# Left_Glove.net
KiCad netlist of a schematic drawn in EAGLE
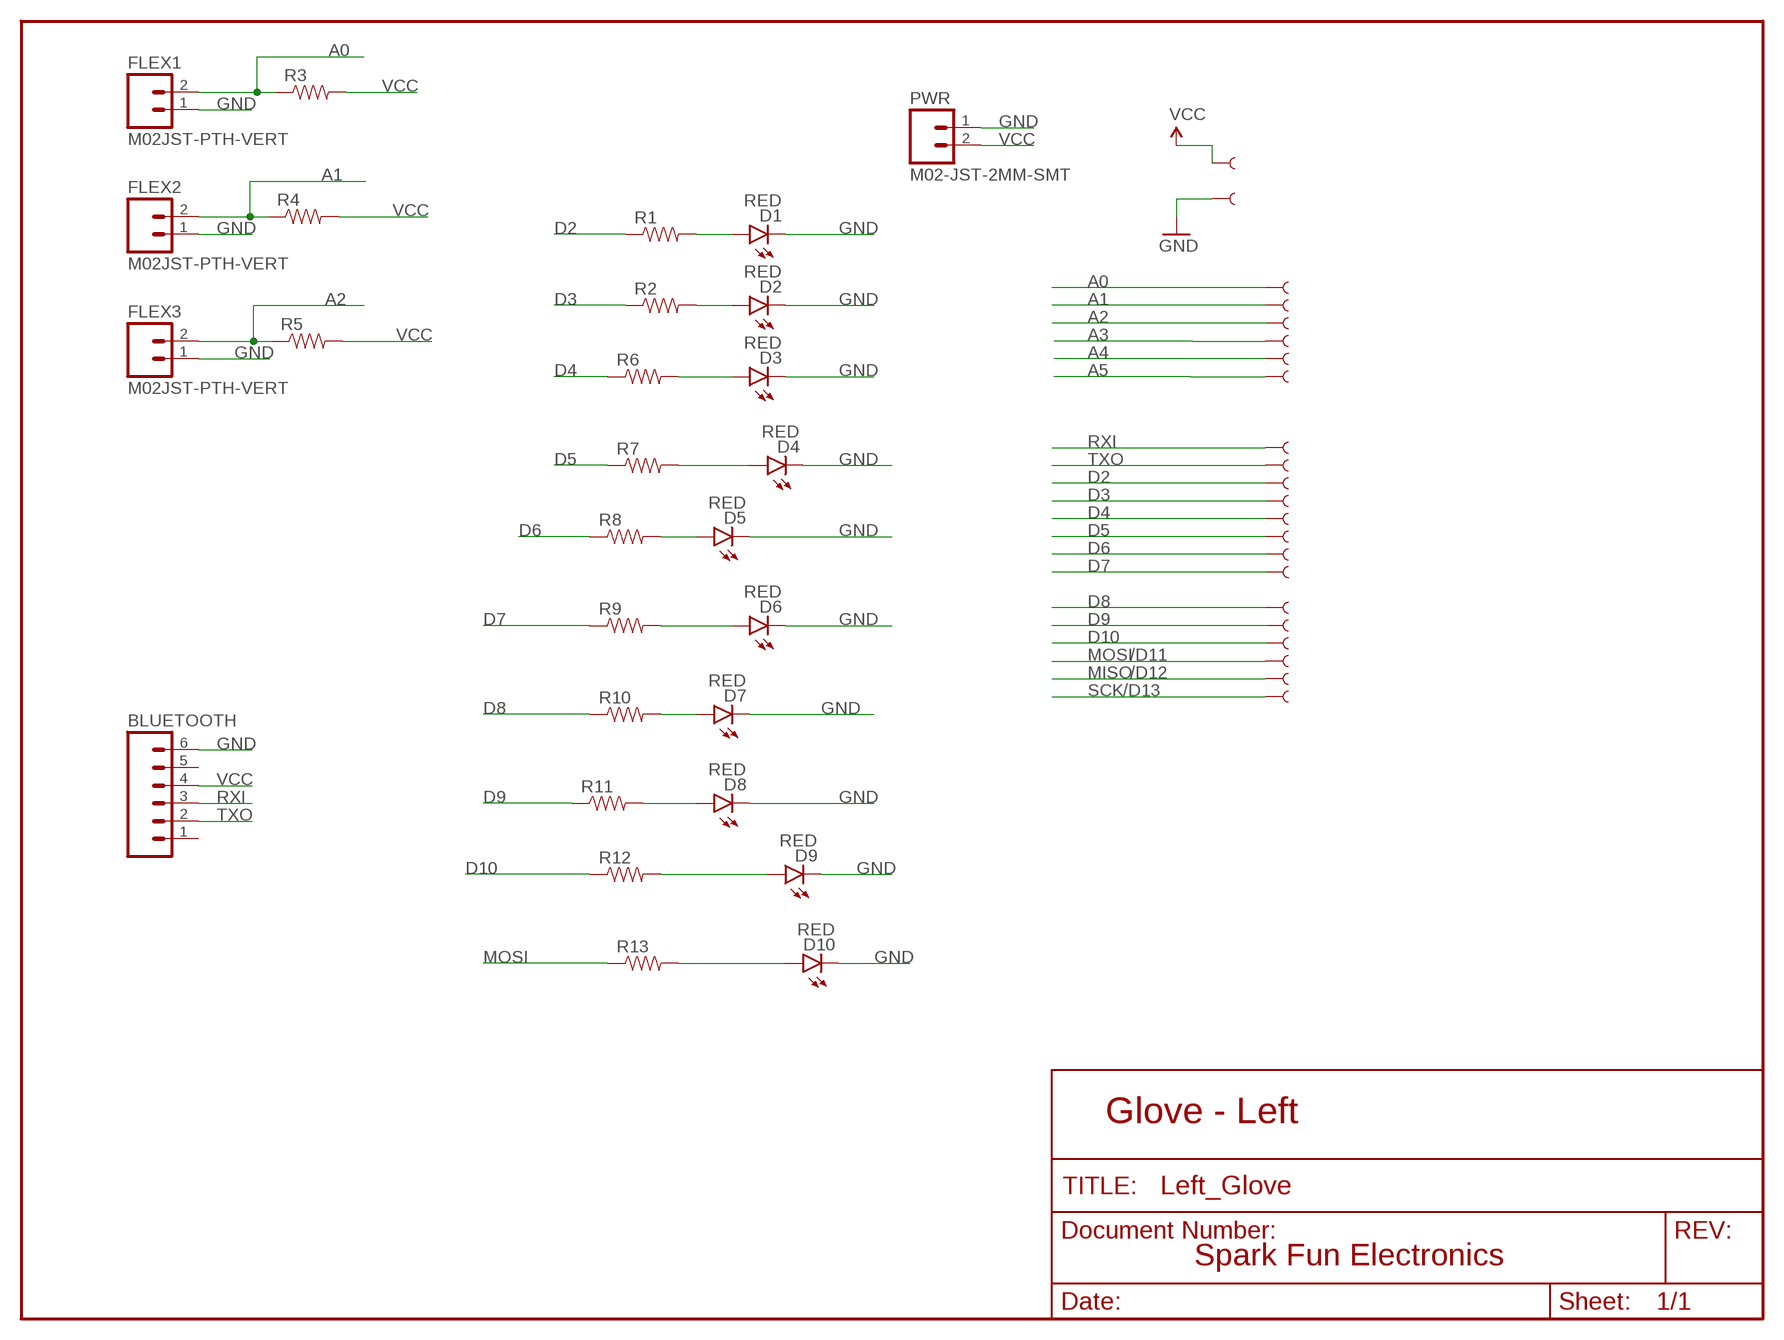
[diagram p0: schematic, sheet 1]

(export (version "E")
  (design (tool "Eeschema 10.0.6"))
  (components
    (comp (ref "BLUETOOTH")
      (value "M06LOCK")
      (footprint "eagle-import:1X06_LOCK")
      (libsource (lib "eagle-import") (part "M06LOCK"))
    )
    (comp (ref "D1")
      (value "RED")
      (footprint "eagle-import:LED-1206")
      (libsource (lib "eagle-import") (part "LED-RED1206"))
    )
    (comp (ref "D2")
      (value "RED")
      (footprint "eagle-import:LED-1206")
      (libsource (lib "eagle-import") (part "LED-RED1206"))
    )
    (comp (ref "D3")
      (value "RED")
      (footprint "eagle-import:LED-1206")
      (libsource (lib "eagle-import") (part "LED-RED1206"))
    )
    (comp (ref "D4")
      (value "RED")
      (footprint "eagle-import:LED-1206")
      (libsource (lib "eagle-import") (part "LED-RED1206"))
    )
    (comp (ref "D5")
      (value "RED")
      (footprint "eagle-import:LED-1206")
      (libsource (lib "eagle-import") (part "LED-RED1206"))
    )
    (comp (ref "D6")
      (value "RED")
      (footprint "eagle-import:LED-1206")
      (libsource (lib "eagle-import") (part "LED-RED1206"))
    )
    (comp (ref "D7")
      (value "RED")
      (footprint "eagle-import:LED-1206")
      (libsource (lib "eagle-import") (part "LED-RED1206"))
    )
    (comp (ref "D8")
      (value "RED")
      (footprint "eagle-import:LED-1206")
      (libsource (lib "eagle-import") (part "LED-RED1206"))
    )
    (comp (ref "D9")
      (value "RED")
      (footprint "eagle-import:LED-1206")
      (libsource (lib "eagle-import") (part "LED-RED1206"))
    )
    (comp (ref "D10")
      (value "RED")
      (footprint "eagle-import:LED-1206")
      (libsource (lib "eagle-import") (part "LED-RED1206"))
    )
    (comp (ref "FLEX1")
      (value "M02JST-PTH-VERT")
      (footprint "eagle-import:JST-2-PTH-VERT")
      (libsource (lib "eagle-import") (part "M02JST-PTH-VERT"))
    )
    (comp (ref "FLEX2")
      (value "M02JST-PTH-VERT")
      (footprint "eagle-import:JST-2-PTH-VERT")
      (libsource (lib "eagle-import") (part "M02JST-PTH-VERT"))
    )
    (comp (ref "FLEX3")
      (value "M02JST-PTH-VERT")
      (footprint "eagle-import:JST-2-PTH-VERT")
      (libsource (lib "eagle-import") (part "M02JST-PTH-VERT"))
    )
    (comp (ref "PWR")
      (value "M02-JST-2MM-SMT")
      (footprint "eagle-import:JST-2-SMD")
      (libsource (lib "eagle-import") (part "M02-JST-2MM-SMT"))
    )
    (comp (ref "R1")
      (value "RESISTOR1206")
      (footprint "eagle-import:1206")
      (libsource (lib "eagle-import") (part "RESISTOR1206"))
    )
    (comp (ref "R2")
      (value "RESISTOR1206")
      (footprint "eagle-import:1206")
      (libsource (lib "eagle-import") (part "RESISTOR1206"))
    )
    (comp (ref "R3")
      (value "RESISTOR1206")
      (footprint "eagle-import:1206")
      (libsource (lib "eagle-import") (part "RESISTOR1206"))
    )
    (comp (ref "R4")
      (value "RESISTOR1206")
      (footprint "eagle-import:1206")
      (libsource (lib "eagle-import") (part "RESISTOR1206"))
    )
    (comp (ref "R5")
      (value "RESISTOR1206")
      (footprint "eagle-import:1206")
      (libsource (lib "eagle-import") (part "RESISTOR1206"))
    )
    (comp (ref "R6")
      (value "RESISTOR1206")
      (footprint "eagle-import:1206")
      (libsource (lib "eagle-import") (part "RESISTOR1206"))
    )
    (comp (ref "R7")
      (value "RESISTOR1206")
      (footprint "eagle-import:1206")
      (libsource (lib "eagle-import") (part "RESISTOR1206"))
    )
    (comp (ref "R8")
      (value "RESISTOR1206")
      (footprint "eagle-import:1206")
      (libsource (lib "eagle-import") (part "RESISTOR1206"))
    )
    (comp (ref "R9")
      (value "RESISTOR1206")
      (footprint "eagle-import:1206")
      (libsource (lib "eagle-import") (part "RESISTOR1206"))
    )
    (comp (ref "R10")
      (value "RESISTOR1206")
      (footprint "eagle-import:1206")
      (libsource (lib "eagle-import") (part "RESISTOR1206"))
    )
    (comp (ref "R11")
      (value "RESISTOR1206")
      (footprint "eagle-import:1206")
      (libsource (lib "eagle-import") (part "RESISTOR1206"))
    )
    (comp (ref "R12")
      (value "RESISTOR1206")
      (footprint "eagle-import:1206")
      (libsource (lib "eagle-import") (part "RESISTOR1206"))
    )
    (comp (ref "R13")
      (value "RESISTOR1206")
      (footprint "eagle-import:1206")
      (libsource (lib "eagle-import") (part "RESISTOR1206"))
    )
    (comp (ref "U$22")
      (value "SEWTAP1")
      (footprint "eagle-import:PETAL-LONG-1")
      (libsource (lib "eagle-import") (part "SEWTAP1"))
    )
    (comp (ref "U$23")
      (value "SEWTAP1")
      (footprint "eagle-import:PETAL-LONG-1")
      (libsource (lib "eagle-import") (part "SEWTAP1"))
    )
    (comp (ref "U$24")
      (value "SEWTAP1")
      (footprint "eagle-import:PETAL-LONG-1")
      (libsource (lib "eagle-import") (part "SEWTAP1"))
    )
    (comp (ref "U$26")
      (value "SEWTAP1")
      (footprint "eagle-import:PETAL-LONG-1")
      (libsource (lib "eagle-import") (part "SEWTAP1"))
    )
    (comp (ref "U$27")
      (value "SEWTAP1")
      (footprint "eagle-import:PETAL-LONG-1")
      (libsource (lib "eagle-import") (part "SEWTAP1"))
    )
    (comp (ref "U$28")
      (value "SEWTAP1")
      (footprint "eagle-import:PETAL-LONG-1")
      (libsource (lib "eagle-import") (part "SEWTAP1"))
    )
    (comp (ref "U$29")
      (value "SEWTAP1")
      (footprint "eagle-import:PETAL-LONG-1")
      (libsource (lib "eagle-import") (part "SEWTAP1"))
    )
    (comp (ref "U$30")
      (value "SEWTAP1")
      (footprint "eagle-import:PETAL-LONG-1")
      (libsource (lib "eagle-import") (part "SEWTAP1"))
    )
    (comp (ref "U$31")
      (value "SEWTAP1")
      (footprint "eagle-import:PETAL-LONG-1")
      (libsource (lib "eagle-import") (part "SEWTAP1"))
    )
    (comp (ref "U$32")
      (value "SEWTAP1")
      (footprint "eagle-import:PETAL-LONG-1")
      (libsource (lib "eagle-import") (part "SEWTAP1"))
    )
    (comp (ref "U$33")
      (value "SEWTAP1")
      (footprint "eagle-import:PETAL-LONG-1")
      (libsource (lib "eagle-import") (part "SEWTAP1"))
    )
    (comp (ref "U$34")
      (value "SEWTAP1")
      (footprint "eagle-import:PETAL-LONG-1")
      (libsource (lib "eagle-import") (part "SEWTAP1"))
    )
    (comp (ref "U$35")
      (value "SEWTAP1")
      (footprint "eagle-import:PETAL-LONG-1")
      (libsource (lib "eagle-import") (part "SEWTAP1"))
    )
    (comp (ref "U$36")
      (value "SEWTAP1")
      (footprint "eagle-import:PETAL-LONG-1")
      (libsource (lib "eagle-import") (part "SEWTAP1"))
    )
    (comp (ref "U$37")
      (value "SEWTAP1")
      (footprint "eagle-import:PETAL-LONG-1")
      (libsource (lib "eagle-import") (part "SEWTAP1"))
    )
    (comp (ref "U$38")
      (value "SEWTAP1")
      (footprint "eagle-import:PETAL-LONG-1")
      (libsource (lib "eagle-import") (part "SEWTAP1"))
    )
    (comp (ref "U$39")
      (value "SEWTAP1")
      (footprint "eagle-import:PETAL-LONG-1")
      (libsource (lib "eagle-import") (part "SEWTAP1"))
    )
    (comp (ref "U$40")
      (value "SEWTAP1")
      (footprint "eagle-import:PETAL-LONG-1")
      (libsource (lib "eagle-import") (part "SEWTAP1"))
    )
    (comp (ref "U$41")
      (value "SEWTAP1")
      (footprint "eagle-import:PETAL-LONG-1")
      (libsource (lib "eagle-import") (part "SEWTAP1"))
    )
    (comp (ref "U$42")
      (value "SEWTAP1")
      (footprint "eagle-import:PETAL-LONG-1")
      (libsource (lib "eagle-import") (part "SEWTAP1"))
    )
    (comp (ref "U$43")
      (value "SEWTAP1")
      (footprint "eagle-import:PETAL-LONG-1")
      (libsource (lib "eagle-import") (part "SEWTAP1"))
    )
    (comp (ref "U$44")
      (value "SEWTAP1")
      (footprint "eagle-import:PETAL-LONG-1")
      (libsource (lib "eagle-import") (part "SEWTAP1"))
    )
  )
  (nets
    (net (code "1") (name "/A0") (class "Default")
      (node (ref "FLEX1") (pin "2") (pinfunction "2_2") (pintype "passive"))
      (node (ref "R3") (pin "1") (pinfunction "1_1") (pintype "passive"))
      (node (ref "U$24") (pin "P$1") (pinfunction "1_P$1") (pintype "bidirectional"))
    )
    (net (code "2") (name "/A1") (class "Default")
      (node (ref "FLEX2") (pin "2") (pinfunction "2_2") (pintype "passive"))
      (node (ref "R4") (pin "1") (pinfunction "1_1") (pintype "passive"))
      (node (ref "U$26") (pin "P$1") (pinfunction "1_P$1") (pintype "bidirectional"))
    )
    (net (code "3") (name "/A2") (class "Default")
      (node (ref "FLEX3") (pin "2") (pinfunction "2_2") (pintype "passive"))
      (node (ref "R5") (pin "1") (pinfunction "1_1") (pintype "passive"))
      (node (ref "U$27") (pin "P$1") (pinfunction "1_P$1") (pintype "bidirectional"))
    )
    (net (code "4") (name "/A3") (class "Default")
      (node (ref "U$28") (pin "P$1") (pinfunction "1_P$1") (pintype "bidirectional"))
    )
    (net (code "5") (name "/A4") (class "Default")
      (node (ref "U$29") (pin "P$1") (pinfunction "1_P$1") (pintype "bidirectional"))
    )
    (net (code "6") (name "/A5") (class "Default")
      (node (ref "U$30") (pin "P$1") (pinfunction "1_P$1") (pintype "bidirectional"))
    )
    (net (code "7") (name "/D2") (class "Default")
      (node (ref "R1") (pin "1") (pinfunction "1_1") (pintype "passive"))
      (node (ref "U$33") (pin "P$1") (pinfunction "1_P$1") (pintype "bidirectional"))
    )
    (net (code "8") (name "/D3") (class "Default")
      (node (ref "R2") (pin "1") (pinfunction "1_1") (pintype "passive"))
      (node (ref "U$34") (pin "P$1") (pinfunction "1_P$1") (pintype "bidirectional"))
    )
    (net (code "9") (name "/D4") (class "Default")
      (node (ref "R6") (pin "1") (pinfunction "1_1") (pintype "passive"))
      (node (ref "U$35") (pin "P$1") (pinfunction "1_P$1") (pintype "bidirectional"))
    )
    (net (code "10") (name "/D5") (class "Default")
      (node (ref "R7") (pin "1") (pinfunction "1_1") (pintype "passive"))
      (node (ref "U$36") (pin "P$1") (pinfunction "1_P$1") (pintype "bidirectional"))
    )
    (net (code "11") (name "/D6") (class "Default")
      (node (ref "R8") (pin "1") (pinfunction "1_1") (pintype "passive"))
      (node (ref "U$37") (pin "P$1") (pinfunction "1_P$1") (pintype "bidirectional"))
    )
    (net (code "12") (name "/D7") (class "Default")
      (node (ref "R9") (pin "1") (pinfunction "1_1") (pintype "passive"))
      (node (ref "U$38") (pin "P$1") (pinfunction "1_P$1") (pintype "bidirectional"))
    )
    (net (code "13") (name "/D8") (class "Default")
      (node (ref "R10") (pin "1") (pinfunction "1_1") (pintype "passive"))
      (node (ref "U$39") (pin "P$1") (pinfunction "1_P$1") (pintype "bidirectional"))
    )
    (net (code "14") (name "/D9") (class "Default")
      (node (ref "R11") (pin "1") (pinfunction "1_1") (pintype "passive"))
      (node (ref "U$40") (pin "P$1") (pinfunction "1_P$1") (pintype "bidirectional"))
    )
    (net (code "15") (name "/D10") (class "Default")
      (node (ref "R12") (pin "1") (pinfunction "1_1") (pintype "passive"))
      (node (ref "U$41") (pin "P$1") (pinfunction "1_P$1") (pintype "bidirectional"))
    )
    (net (code "16") (name "/MISO") (class "Default")
      (node (ref "U$43") (pin "P$1") (pinfunction "1_P$1") (pintype "bidirectional"))
    )
    (net (code "17") (name "/MOSI") (class "Default")
      (node (ref "R13") (pin "1") (pinfunction "1_1") (pintype "passive"))
      (node (ref "U$42") (pin "P$1") (pinfunction "1_P$1") (pintype "bidirectional"))
    )
    (net (code "18") (name "/RXI") (class "Default")
      (node (ref "BLUETOOTH") (pin "3") (pinfunction "3_3") (pintype "passive"))
      (node (ref "U$31") (pin "P$1") (pinfunction "1_P$1") (pintype "bidirectional"))
    )
    (net (code "19") (name "/SCK") (class "Default")
      (node (ref "U$44") (pin "P$1") (pinfunction "1_P$1") (pintype "bidirectional"))
    )
    (net (code "20") (name "/TXO") (class "Default")
      (node (ref "BLUETOOTH") (pin "2") (pinfunction "2_2") (pintype "passive"))
      (node (ref "U$32") (pin "P$1") (pinfunction "1_P$1") (pintype "bidirectional"))
    )
    (net (code "21") (name "GND") (class "Default")
      (node (ref "BLUETOOTH") (pin "6") (pinfunction "6_6") (pintype "passive"))
      (node (ref "D1") (pin "C") (pinfunction "C_C") (pintype "passive"))
      (node (ref "D10") (pin "C") (pinfunction "C_C") (pintype "passive"))
      (node (ref "D2") (pin "C") (pinfunction "C_C") (pintype "passive"))
      (node (ref "D3") (pin "C") (pinfunction "C_C") (pintype "passive"))
      (node (ref "D4") (pin "C") (pinfunction "C_C") (pintype "passive"))
      (node (ref "D5") (pin "C") (pinfunction "C_C") (pintype "passive"))
      (node (ref "D6") (pin "C") (pinfunction "C_C") (pintype "passive"))
      (node (ref "D7") (pin "C") (pinfunction "C_C") (pintype "passive"))
      (node (ref "D8") (pin "C") (pinfunction "C_C") (pintype "passive"))
      (node (ref "D9") (pin "C") (pinfunction "C_C") (pintype "passive"))
      (node (ref "FLEX1") (pin "1") (pinfunction "1_1") (pintype "passive"))
      (node (ref "FLEX2") (pin "1") (pinfunction "1_1") (pintype "passive"))
      (node (ref "FLEX3") (pin "1") (pinfunction "1_1") (pintype "passive"))
      (node (ref "PWR") (pin "1") (pinfunction "2_1") (pintype "passive"))
      (node (ref "U$23") (pin "P$1") (pinfunction "1_P$1") (pintype "bidirectional"))
    )
    (net (code "22") (name "Net-(D1-PadA)") (class "Default")
      (node (ref "D1") (pin "A") (pinfunction "A_A") (pintype "passive"))
      (node (ref "R1") (pin "2") (pinfunction "2_2") (pintype "passive"))
    )
    (net (code "23") (name "Net-(D2-PadA)") (class "Default")
      (node (ref "D2") (pin "A") (pinfunction "A_A") (pintype "passive"))
      (node (ref "R2") (pin "2") (pinfunction "2_2") (pintype "passive"))
    )
    (net (code "24") (name "Net-(D3-PadA)") (class "Default")
      (node (ref "D3") (pin "A") (pinfunction "A_A") (pintype "passive"))
      (node (ref "R6") (pin "2") (pinfunction "2_2") (pintype "passive"))
    )
    (net (code "25") (name "Net-(D4-PadA)") (class "Default")
      (node (ref "D4") (pin "A") (pinfunction "A_A") (pintype "passive"))
      (node (ref "R7") (pin "2") (pinfunction "2_2") (pintype "passive"))
    )
    (net (code "26") (name "Net-(D5-PadA)") (class "Default")
      (node (ref "D5") (pin "A") (pinfunction "A_A") (pintype "passive"))
      (node (ref "R8") (pin "2") (pinfunction "2_2") (pintype "passive"))
    )
    (net (code "27") (name "Net-(D6-PadA)") (class "Default")
      (node (ref "D6") (pin "A") (pinfunction "A_A") (pintype "passive"))
      (node (ref "R9") (pin "2") (pinfunction "2_2") (pintype "passive"))
    )
    (net (code "28") (name "Net-(D7-PadA)") (class "Default")
      (node (ref "D7") (pin "A") (pinfunction "A_A") (pintype "passive"))
      (node (ref "R10") (pin "2") (pinfunction "2_2") (pintype "passive"))
    )
    (net (code "29") (name "Net-(D8-PadA)") (class "Default")
      (node (ref "D8") (pin "A") (pinfunction "A_A") (pintype "passive"))
      (node (ref "R11") (pin "2") (pinfunction "2_2") (pintype "passive"))
    )
    (net (code "30") (name "Net-(D9-PadA)") (class "Default")
      (node (ref "D9") (pin "A") (pinfunction "A_A") (pintype "passive"))
      (node (ref "R12") (pin "2") (pinfunction "2_2") (pintype "passive"))
    )
    (net (code "31") (name "Net-(D10-PadA)") (class "Default")
      (node (ref "D10") (pin "A") (pinfunction "A_A") (pintype "passive"))
      (node (ref "R13") (pin "2") (pinfunction "2_2") (pintype "passive"))
    )
    (net (code "32") (name "VCC") (class "Default")
      (node (ref "BLUETOOTH") (pin "4") (pinfunction "4_4") (pintype "passive"))
      (node (ref "PWR") (pin "2") (pinfunction "1_2") (pintype "passive"))
      (node (ref "R3") (pin "2") (pinfunction "2_2") (pintype "passive"))
      (node (ref "R4") (pin "2") (pinfunction "2_2") (pintype "passive"))
      (node (ref "R5") (pin "2") (pinfunction "2_2") (pintype "passive"))
      (node (ref "U$22") (pin "P$1") (pinfunction "1_P$1") (pintype "bidirectional"))
    )
    (net (code "33") (name "unconnected-(BLUETOOTH-Pad1)") (class "Default")
      (node (ref "BLUETOOTH") (pin "1") (pinfunction "1_1") (pintype "passive"))
    )
    (net (code "34") (name "unconnected-(BLUETOOTH-Pad5)") (class "Default")
      (node (ref "BLUETOOTH") (pin "5") (pinfunction "5_5") (pintype "passive"))
    )
  )
)
